# plate.net
KiCad netlist of a schematic drawn in EAGLE
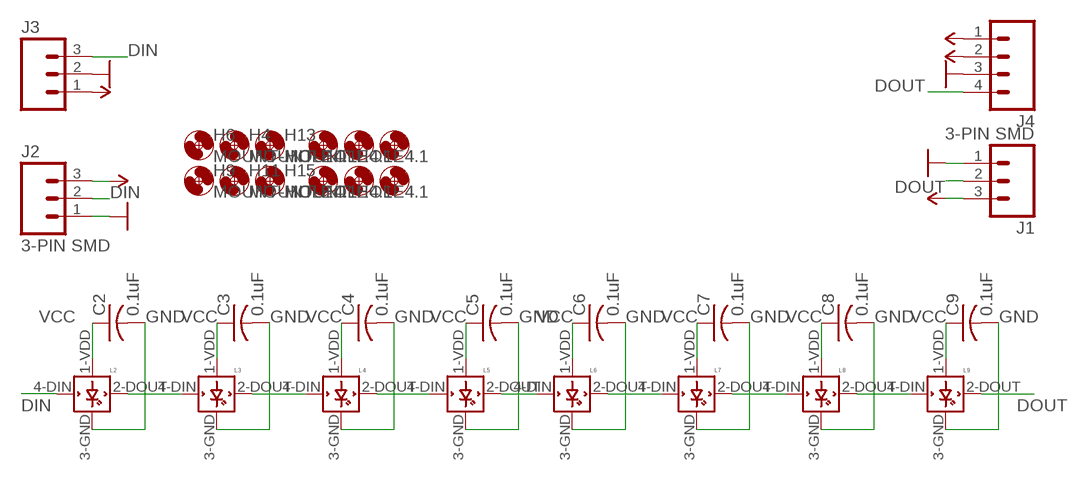
[diagram p0: schematic, sheet 1]

(export (version "E")
  (design (tool "Eeschema 10.0.6"))
  (components
    (comp (ref "C2")
      (value "0.1uF")
      (footprint "eagle-import:C0603K")
      (libsource (lib "eagle-import") (part "C-USC0603K"))
    )
    (comp (ref "C3")
      (value "0.1uF")
      (footprint "eagle-import:C0603K")
      (libsource (lib "eagle-import") (part "C-USC0603K"))
    )
    (comp (ref "C4")
      (value "0.1uF")
      (footprint "eagle-import:C0603K")
      (libsource (lib "eagle-import") (part "C-USC0603K"))
    )
    (comp (ref "C5")
      (value "0.1uF")
      (footprint "eagle-import:C0603K")
      (libsource (lib "eagle-import") (part "C-USC0603K"))
    )
    (comp (ref "C6")
      (value "0.1uF")
      (footprint "eagle-import:C0603K")
      (libsource (lib "eagle-import") (part "C-USC0603K"))
    )
    (comp (ref "C7")
      (value "0.1uF")
      (footprint "eagle-import:C0603K")
      (libsource (lib "eagle-import") (part "C-USC0603K"))
    )
    (comp (ref "C8")
      (value "0.1uF")
      (footprint "eagle-import:C0603K")
      (libsource (lib "eagle-import") (part "C-USC0603K"))
    )
    (comp (ref "C9")
      (value "0.1uF")
      (footprint "eagle-import:C0603K")
      (libsource (lib "eagle-import") (part "C-USC0603K"))
    )
    (comp (ref "H1")
      (value "MOUNT-HOLE4.1")
      (footprint "eagle-import:4,1")
      (libsource (lib "eagle-import") (part "MOUNT-HOLE4.1"))
    )
    (comp (ref "H2")
      (value "MOUNT-HOLE4.1")
      (footprint "eagle-import:4,1")
      (libsource (lib "eagle-import") (part "MOUNT-HOLE4.1"))
    )
    (comp (ref "H3")
      (value "MOUNT-HOLE4.1")
      (footprint "eagle-import:4,1")
      (libsource (lib "eagle-import") (part "MOUNT-HOLE4.1"))
    )
    (comp (ref "H4")
      (value "MOUNT-HOLE4.1")
      (footprint "eagle-import:4,1")
      (libsource (lib "eagle-import") (part "MOUNT-HOLE4.1"))
    )
    (comp (ref "H5")
      (value "MOUNT-HOLE4.1")
      (footprint "eagle-import:4,1")
      (libsource (lib "eagle-import") (part "MOUNT-HOLE4.1"))
    )
    (comp (ref "H6")
      (value "MOUNT-HOLE4.1")
      (footprint "eagle-import:4,1")
      (libsource (lib "eagle-import") (part "MOUNT-HOLE4.1"))
    )
    (comp (ref "H7")
      (value "MOUNT-HOLE4.1")
      (footprint "eagle-import:4,1")
      (libsource (lib "eagle-import") (part "MOUNT-HOLE4.1"))
    )
    (comp (ref "H8")
      (value "MOUNT-HOLE4.1")
      (footprint "eagle-import:4,1")
      (libsource (lib "eagle-import") (part "MOUNT-HOLE4.1"))
    )
    (comp (ref "H9")
      (value "MOUNT-HOLE4.1")
      (footprint "eagle-import:4,1")
      (libsource (lib "eagle-import") (part "MOUNT-HOLE4.1"))
    )
    (comp (ref "H11")
      (value "MOUNT-HOLE4.1")
      (footprint "eagle-import:4,1")
      (libsource (lib "eagle-import") (part "MOUNT-HOLE4.1"))
    )
    (comp (ref "H13")
      (value "MOUNT-HOLE4.1")
      (footprint "eagle-import:4,1")
      (libsource (lib "eagle-import") (part "MOUNT-HOLE4.1"))
    )
    (comp (ref "H15")
      (value "MOUNT-HOLE4.1")
      (footprint "eagle-import:4,1")
      (libsource (lib "eagle-import") (part "MOUNT-HOLE4.1"))
    )
    (comp (ref "J1")
      (value "3-PIN SMD")
      (footprint "eagle-import:JST-3-PTH-VERT")
      (libsource (lib "eagle-import") (part "M03JST-PTH-VERT"))
    )
    (comp (ref "J2")
      (value "3-PIN SMD")
      (footprint "eagle-import:JST-3-PTH-VERT")
      (libsource (lib "eagle-import") (part "M03JST-PTH-VERT"))
    )
    (comp (ref "J3")
      (value "M03JST-PTH-VERT")
      (footprint "eagle-import:JST-3-PTH-VERT")
      (libsource (lib "eagle-import") (part "M03JST-PTH-VERT"))
    )
    (comp (ref "J4")
      (value "M04JST-PTH-VERT")
      (footprint "eagle-import:JST-4-PTH-VERT")
      (libsource (lib "eagle-import") (part "M04JST-PTH-VERT"))
    )
    (comp (ref "L2")
      (value "WS2812B")
      (footprint "eagle-import:WS2812B")
      (libsource (lib "eagle-import") (part "WS2812B"))
    )
    (comp (ref "L3")
      (value "WS2812B")
      (footprint "eagle-import:WS2812B")
      (libsource (lib "eagle-import") (part "WS2812B"))
    )
    (comp (ref "L4")
      (value "WS2812B")
      (footprint "eagle-import:WS2812B")
      (libsource (lib "eagle-import") (part "WS2812B"))
    )
    (comp (ref "L5")
      (value "WS2812B")
      (footprint "eagle-import:WS2812B")
      (libsource (lib "eagle-import") (part "WS2812B"))
    )
    (comp (ref "L6")
      (value "WS2812B")
      (footprint "eagle-import:WS2812B")
      (libsource (lib "eagle-import") (part "WS2812B"))
    )
    (comp (ref "L7")
      (value "WS2812B")
      (footprint "eagle-import:WS2812B")
      (libsource (lib "eagle-import") (part "WS2812B"))
    )
    (comp (ref "L8")
      (value "WS2812B")
      (footprint "eagle-import:WS2812B")
      (libsource (lib "eagle-import") (part "WS2812B"))
    )
    (comp (ref "L9")
      (value "WS2812B")
      (footprint "eagle-import:WS2812B")
      (libsource (lib "eagle-import") (part "WS2812B"))
    )
  )
  (nets
    (net (code "1") (name "/DIN") (class "Default")
      (node (ref "J2") (pin "2") (pinfunction "2_2") (pintype "passive"))
      (node (ref "J3") (pin "3") (pinfunction "3_3") (pintype "passive"))
      (node (ref "L2") (pin "4-DIN") (pinfunction "DIN_4-DIN") (pintype "input"))
    )
    (net (code "2") (name "/DOUT") (class "Default")
      (node (ref "J1") (pin "2") (pinfunction "2_2") (pintype "passive"))
      (node (ref "J4") (pin "4") (pinfunction "4_4") (pintype "passive"))
      (node (ref "L9") (pin "2-DOUT") (pinfunction "DOUT_2-DOUT") (pintype "output"))
    )
    (net (code "3") (name "GND") (class "Default")
      (node (ref "C2") (pin "2") (pinfunction "2_2") (pintype "passive"))
      (node (ref "C3") (pin "2") (pinfunction "2_2") (pintype "passive"))
      (node (ref "C4") (pin "2") (pinfunction "2_2") (pintype "passive"))
      (node (ref "C5") (pin "2") (pinfunction "2_2") (pintype "passive"))
      (node (ref "C6") (pin "2") (pinfunction "2_2") (pintype "passive"))
      (node (ref "C7") (pin "2") (pinfunction "2_2") (pintype "passive"))
      (node (ref "C8") (pin "2") (pinfunction "2_2") (pintype "passive"))
      (node (ref "C9") (pin "2") (pinfunction "2_2") (pintype "passive"))
      (node (ref "J1") (pin "1") (pinfunction "1_1") (pintype "passive"))
      (node (ref "J2") (pin "1") (pinfunction "1_1") (pintype "passive"))
      (node (ref "J3") (pin "2") (pinfunction "2_2") (pintype "passive"))
      (node (ref "J4") (pin "3") (pinfunction "3_3") (pintype "passive"))
      (node (ref "L2") (pin "3-GND") (pinfunction "GND_3-GND") (pintype "bidirectional"))
      (node (ref "L3") (pin "3-GND") (pinfunction "GND_3-GND") (pintype "bidirectional"))
      (node (ref "L4") (pin "3-GND") (pinfunction "GND_3-GND") (pintype "bidirectional"))
      (node (ref "L5") (pin "3-GND") (pinfunction "GND_3-GND") (pintype "bidirectional"))
      (node (ref "L6") (pin "3-GND") (pinfunction "GND_3-GND") (pintype "bidirectional"))
      (node (ref "L7") (pin "3-GND") (pinfunction "GND_3-GND") (pintype "bidirectional"))
      (node (ref "L8") (pin "3-GND") (pinfunction "GND_3-GND") (pintype "bidirectional"))
      (node (ref "L9") (pin "3-GND") (pinfunction "GND_3-GND") (pintype "bidirectional"))
    )
    (net (code "4") (name "Net-(L2-DOUT)") (class "Default")
      (node (ref "L2") (pin "2-DOUT") (pinfunction "DOUT_2-DOUT") (pintype "output"))
      (node (ref "L3") (pin "4-DIN") (pinfunction "DIN_4-DIN") (pintype "input"))
    )
    (net (code "5") (name "Net-(L3-DOUT)") (class "Default")
      (node (ref "L3") (pin "2-DOUT") (pinfunction "DOUT_2-DOUT") (pintype "output"))
      (node (ref "L4") (pin "4-DIN") (pinfunction "DIN_4-DIN") (pintype "input"))
    )
    (net (code "6") (name "Net-(L4-DOUT)") (class "Default")
      (node (ref "L4") (pin "2-DOUT") (pinfunction "DOUT_2-DOUT") (pintype "output"))
      (node (ref "L5") (pin "4-DIN") (pinfunction "DIN_4-DIN") (pintype "input"))
    )
    (net (code "7") (name "Net-(L5-DOUT)") (class "Default")
      (node (ref "L5") (pin "2-DOUT") (pinfunction "DOUT_2-DOUT") (pintype "output"))
      (node (ref "L6") (pin "4-DIN") (pinfunction "DIN_4-DIN") (pintype "input"))
    )
    (net (code "8") (name "Net-(L6-DOUT)") (class "Default")
      (node (ref "L6") (pin "2-DOUT") (pinfunction "DOUT_2-DOUT") (pintype "output"))
      (node (ref "L7") (pin "4-DIN") (pinfunction "DIN_4-DIN") (pintype "input"))
    )
    (net (code "9") (name "Net-(L7-DOUT)") (class "Default")
      (node (ref "L7") (pin "2-DOUT") (pinfunction "DOUT_2-DOUT") (pintype "output"))
      (node (ref "L8") (pin "4-DIN") (pinfunction "DIN_4-DIN") (pintype "input"))
    )
    (net (code "10") (name "Net-(L8-DOUT)") (class "Default")
      (node (ref "L8") (pin "2-DOUT") (pinfunction "DOUT_2-DOUT") (pintype "output"))
      (node (ref "L9") (pin "4-DIN") (pinfunction "DIN_4-DIN") (pintype "input"))
    )
    (net (code "11") (name "VCC") (class "Default")
      (node (ref "C2") (pin "1") (pinfunction "1_1") (pintype "passive"))
      (node (ref "C3") (pin "1") (pinfunction "1_1") (pintype "passive"))
      (node (ref "C4") (pin "1") (pinfunction "1_1") (pintype "passive"))
      (node (ref "C5") (pin "1") (pinfunction "1_1") (pintype "passive"))
      (node (ref "C6") (pin "1") (pinfunction "1_1") (pintype "passive"))
      (node (ref "C7") (pin "1") (pinfunction "1_1") (pintype "passive"))
      (node (ref "C8") (pin "1") (pinfunction "1_1") (pintype "passive"))
      (node (ref "C9") (pin "1") (pinfunction "1_1") (pintype "passive"))
      (node (ref "J1") (pin "3") (pinfunction "3_3") (pintype "passive"))
      (node (ref "J2") (pin "3") (pinfunction "3_3") (pintype "passive"))
      (node (ref "J3") (pin "1") (pinfunction "1_1") (pintype "passive"))
      (node (ref "J4") (pin "1") (pinfunction "1_1") (pintype "passive"))
      (node (ref "J4") (pin "2") (pinfunction "2_2") (pintype "passive"))
      (node (ref "L2") (pin "1-VDD") (pinfunction "VDD_1-VDD") (pintype "bidirectional"))
      (node (ref "L3") (pin "1-VDD") (pinfunction "VDD_1-VDD") (pintype "bidirectional"))
      (node (ref "L4") (pin "1-VDD") (pinfunction "VDD_1-VDD") (pintype "bidirectional"))
      (node (ref "L5") (pin "1-VDD") (pinfunction "VDD_1-VDD") (pintype "bidirectional"))
      (node (ref "L6") (pin "1-VDD") (pinfunction "VDD_1-VDD") (pintype "bidirectional"))
      (node (ref "L7") (pin "1-VDD") (pinfunction "VDD_1-VDD") (pintype "bidirectional"))
      (node (ref "L8") (pin "1-VDD") (pinfunction "VDD_1-VDD") (pintype "bidirectional"))
      (node (ref "L9") (pin "1-VDD") (pinfunction "VDD_1-VDD") (pintype "bidirectional"))
    )
  )
)
